# CONFIGURATION_STORAGE_USER_LEDS_BUTTONS.net
KiCad netlist of a schematic drawn in Altium Designer
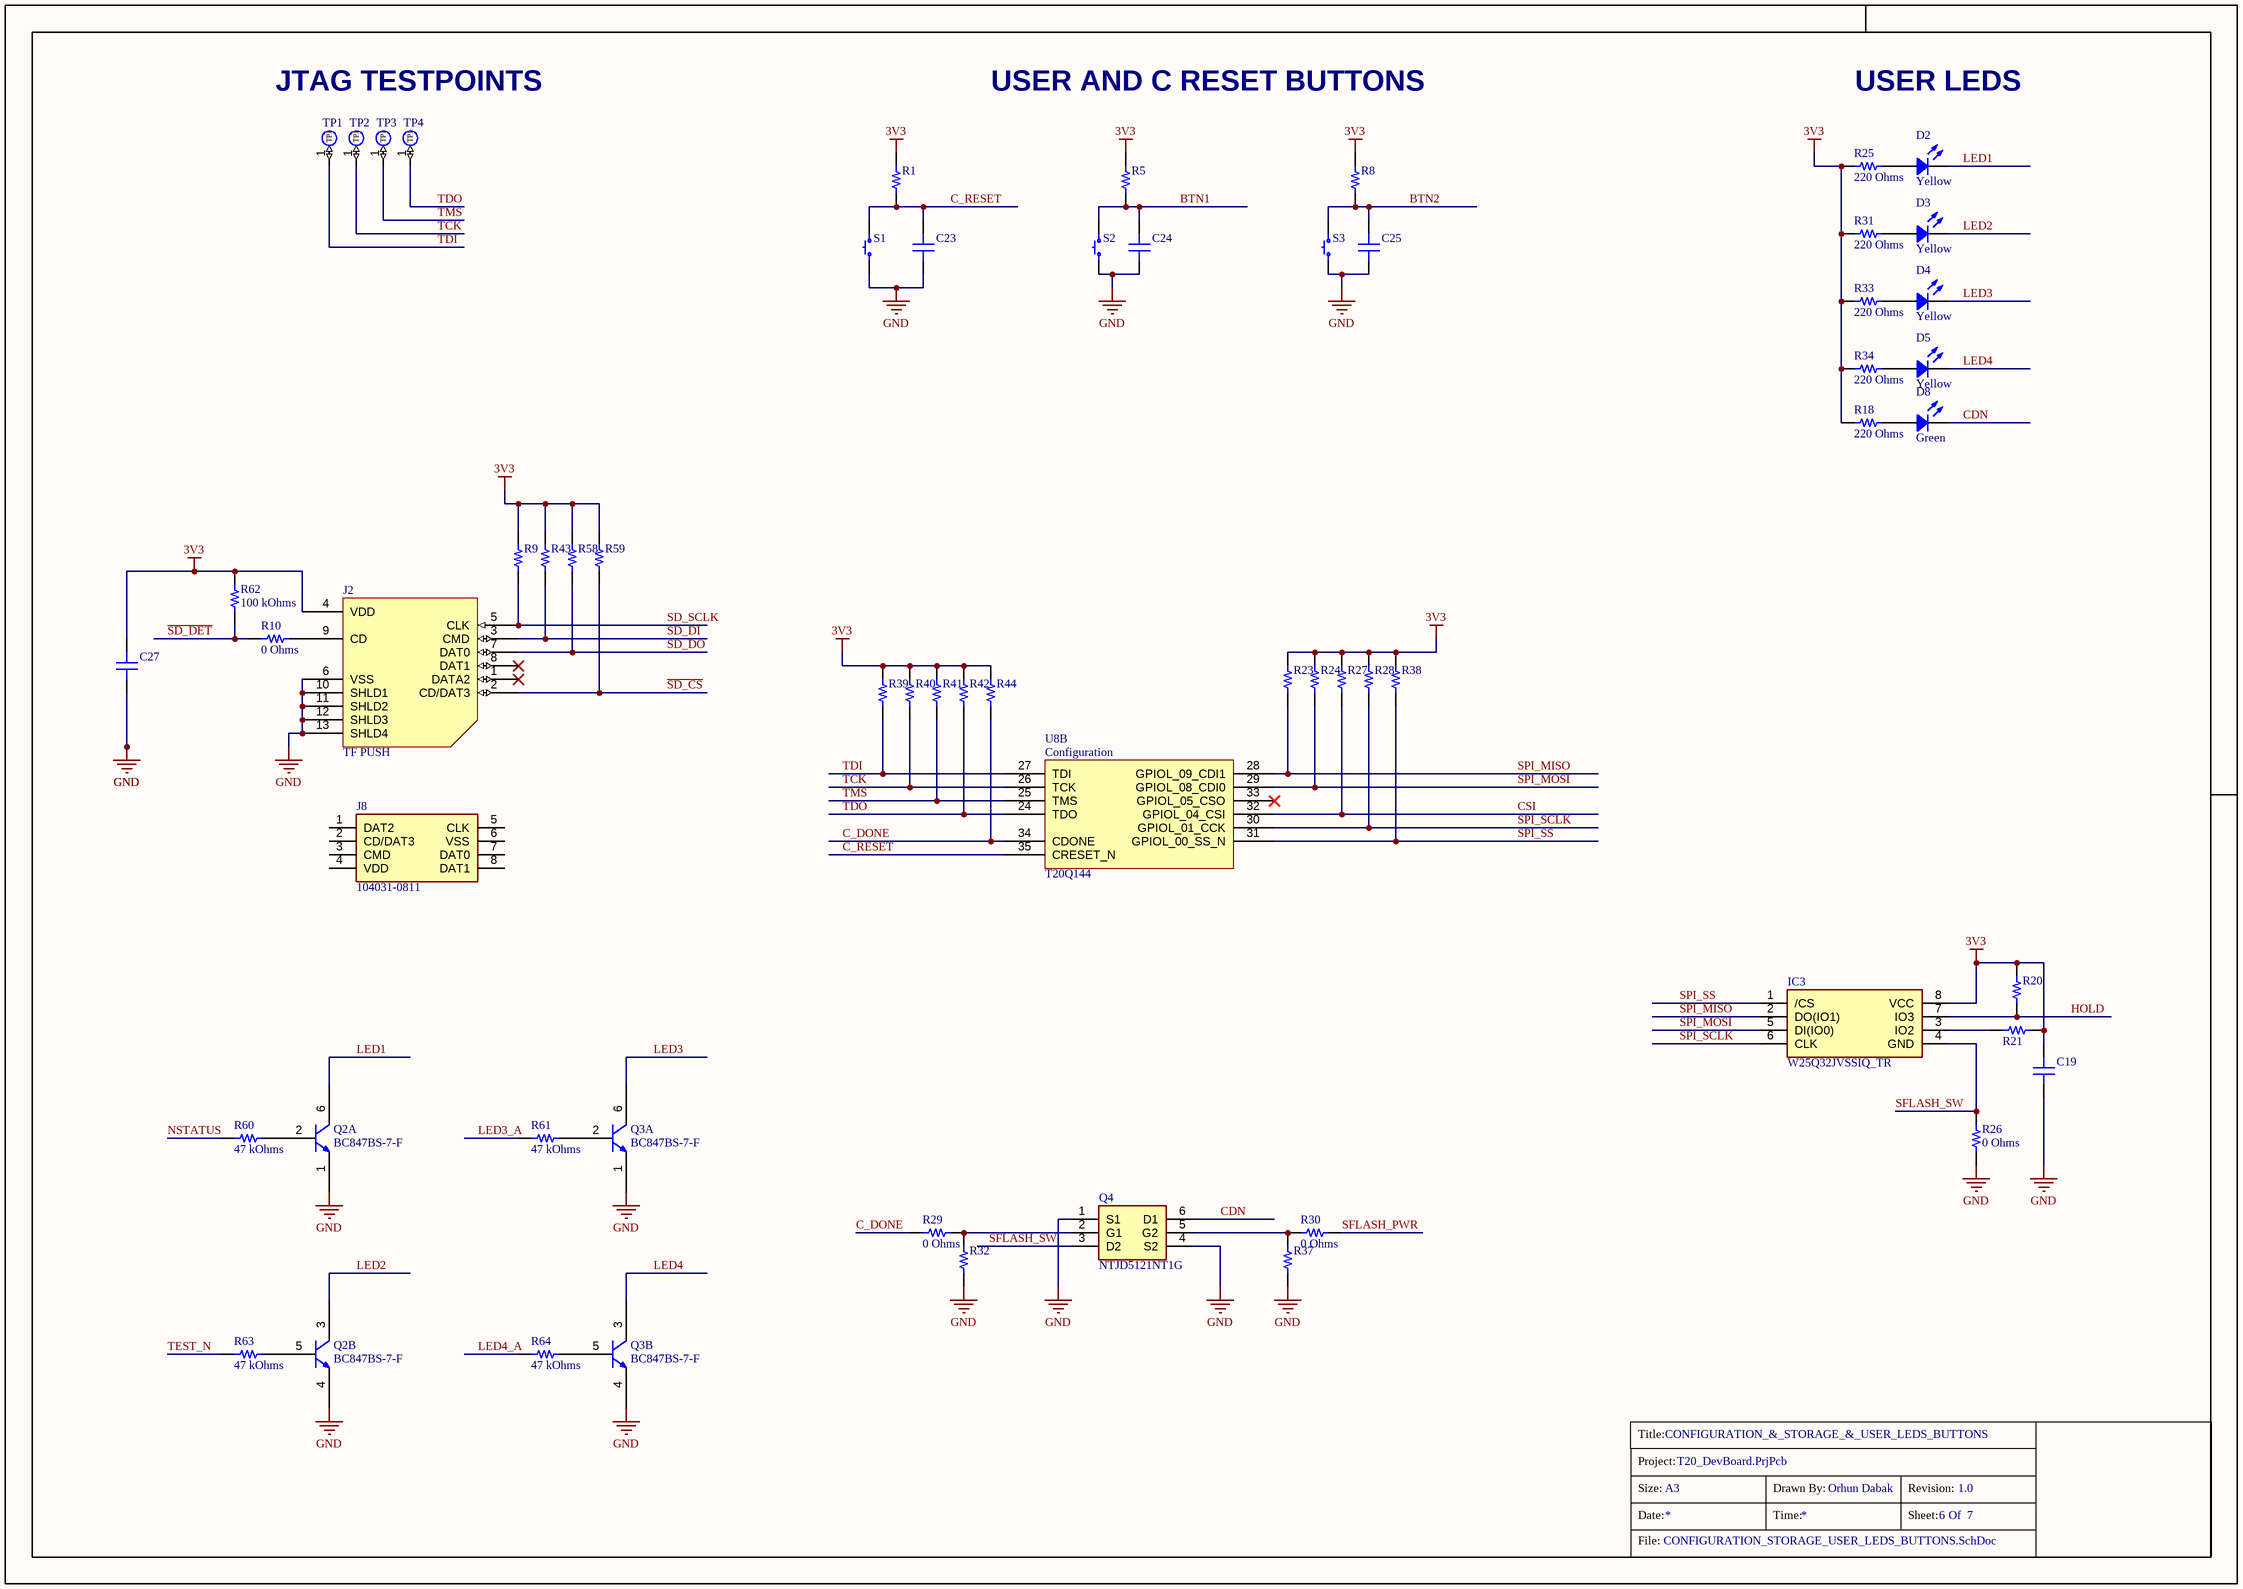
[diagram p0: CONFIGURATION_STORAGE_USER_LEDS_BUTTONS.SchDoc]

(export (version "E")
  (design (tool "Eeschema 10.0.6"))
  (components
    (comp (ref "C19")
      (value "0.1 µF")
      (footprint "CAP 0402_1005")
      (description "CAP CER 0.1UF 10V X7R 0402")
      (fields (field (name "PART NUMBER") "CC0402KRX7R6BB104") (field (name "MANUFACTURER") "Yageo"))
      (libsource (lib "Celestial Altium Library - altium_library") (part "Capacitor"))
    )
    (comp (ref "C23")
      (value "10 µF")
      (footprint "CAP 0402_1005")
      (description "CAP CER 10UF 10V X5R 0402")
      (fields
        (field (name "PART NUMBER") "GRM155R61A106ME11D")
        (field (name "MANUFACTURER") "Murata Electronics")
      )
      (libsource (lib "Celestial Altium Library - altium_library") (part "Capacitor"))
    )
    (comp (ref "C24")
      (value "10 µF")
      (footprint "CAP 0402_1005")
      (description "CAP CER 10UF 10V X5R 0402")
      (fields
        (field (name "PART NUMBER") "GRM155R61A106ME11D")
        (field (name "MANUFACTURER") "Murata Electronics")
      )
      (libsource (lib "Celestial Altium Library - altium_library") (part "Capacitor"))
    )
    (comp (ref "C25")
      (value "10 µF")
      (footprint "CAP 0402_1005")
      (description "CAP CER 10UF 10V X5R 0402")
      (fields
        (field (name "PART NUMBER") "GRM155R61A106ME11D")
        (field (name "MANUFACTURER") "Murata Electronics")
      )
      (libsource (lib "Celestial Altium Library - altium_library") (part "Capacitor"))
    )
    (comp (ref "C27")
      (value "0.1 µF")
      (footprint "CAP 0402_1005")
      (description "CAP CER 0.1UF 10V X7R 0402")
      (fields (field (name "PART NUMBER") "CC0402KRX7R6BB104") (field (name "MANUFACTURER") "Yageo"))
      (libsource (lib "Celestial Altium Library - altium_library") (part "Capacitor"))
    )
    (comp (ref "D2")
      (value "Yellow")
      (footprint "LED 0603_1608 YELLOW")
      (description "LED YELLOW DIFFUSED SMD")
      (fields
        (field (name "PART NUMBER") "SML-LX0603YW-TR")
        (field (name "MANUFACTURER") "Lumex Opto/Components Inc.")
      )
      (libsource (lib "Celestial Altium Library - altium_library") (part "LED"))
    )
    (comp (ref "D3")
      (value "Yellow")
      (footprint "LED 0603_1608 YELLOW")
      (description "LED YELLOW DIFFUSED SMD")
      (fields
        (field (name "PART NUMBER") "SML-LX0603YW-TR")
        (field (name "MANUFACTURER") "Lumex Opto/Components Inc.")
      )
      (libsource (lib "Celestial Altium Library - altium_library") (part "LED"))
    )
    (comp (ref "D4")
      (value "Yellow")
      (footprint "LED 0603_1608 YELLOW")
      (description "LED YELLOW DIFFUSED SMD")
      (fields
        (field (name "PART NUMBER") "SML-LX0603YW-TR")
        (field (name "MANUFACTURER") "Lumex Opto/Components Inc.")
      )
      (libsource (lib "Celestial Altium Library - altium_library") (part "LED"))
    )
    (comp (ref "D5")
      (value "Yellow")
      (footprint "LED 0603_1608 YELLOW")
      (description "LED YELLOW DIFFUSED SMD")
      (fields
        (field (name "PART NUMBER") "SML-LX0603YW-TR")
        (field (name "MANUFACTURER") "Lumex Opto/Components Inc.")
      )
      (libsource (lib "Celestial Altium Library - altium_library") (part "LED"))
    )
    (comp (ref "D8")
      (value "Green")
      (footprint "LED 0603_1608 GREEN")
      (description "LED SM 0603 3V -/1000/-MCD GREEN")
      (fields
        (field (name "PART NUMBER") "LSM0603453V")
        (field (name "MANUFACTURER") "Visual Communications Company - VCC")
      )
      (libsource (lib "Celestial Altium Library - altium_library") (part "LED"))
    )
    (comp (ref "IC3")
      (value "W25Q32JVSSIQ_TR")
      (footprint "SamacSys:SOIC127P790X216-8N")
      (description "Integrated Circuit")
      (fields
        (field (name "MANUFACTURER_PART_NUMBER") "W25Q32JVSSIQ TR")
        (field (name "MOUSER PART NUMBER") "454-W25Q32JVSSIQTR")
      )
      (libsource (lib "SamacSys") (part "W25Q32JVSSIQ_TR"))
    )
    (comp (ref "J2")
      (value "TF PUSH")
      (footprint "TF PUSH")
      (description "-20℃~+90℃ 2mm Deck MicroSD card (TF card) Self bomb SMD SD Card Connectors ROHS")
      (fields (field (name "MANUFACTURER") "SHOU HAN") (field (name "LCSC PART NUMBER") "C393941"))
      (libsource (lib "T8_devkit_PCB") (part "TF PUSH"))
    )
    (comp (ref "J8")
      (value "104031-0811")
      (footprint "SamacSys:1040310811")
      (description "Connector")
      (fields (field (name "MOUSER PART NUMBER") "538-104031-0811"))
      (libsource (lib "*") (part "104031-0811"))
    )
    (comp (ref "Q2")
      (value "BC847BS-7-F")
      (footprint "BC847BS-7-F-Footprint-1")
      (description "2NPN Ic=100mA Vceo=45V hfe=200~450 P=200mW SOT363")
      (libsource (lib "Kocaeli University") (part "BC847BS-7-F-Symbol-1"))
    )
    (comp (ref "Q3")
      (value "BC847BS-7-F")
      (footprint "BC847BS-7-F-Footprint-1")
      (description "2NPN Ic=100mA Vceo=45V hfe=200~450 P=200mW SOT363")
      (libsource (lib "Kocaeli University") (part "BC847BS-7-F-Symbol-1"))
    )
    (comp (ref "Q4")
      (value "NTJD5121NT1G")
      (footprint "SamacSys:SOT65P210X110-6N")
      (description "Transistor")
      (fields (field (name "MOUSER PART NUMBER") "863-NTJD5121NT1G"))
      (libsource (lib "SamacSys") (part "NTJD5121NT1G"))
    )
    (comp (ref "R1")
      (value "10 kOhms")
      (footprint "RES 0402_1005")
      (description "RES 10K OHM 0.1% 1/10W 0402")
      (fields
        (field (name "PART NUMBER") "RP73PF1E10KBTD")
        (field (name "MANUFACTURER") "TE Connectivity Passive Product")
      )
      (libsource (lib "Celestial Altium Library - altium_library") (part "Resistor"))
    )
    (comp (ref "R5")
      (value "10 kOhms")
      (footprint "RES 0402_1005")
      (description "RES 10K OHM 0.1% 1/10W 0402")
      (fields
        (field (name "PART NUMBER") "RP73PF1E10KBTD")
        (field (name "MANUFACTURER") "TE Connectivity Passive Product")
      )
      (libsource (lib "Celestial Altium Library - altium_library") (part "Resistor"))
    )
    (comp (ref "R8")
      (value "10 kOhms")
      (footprint "RES 0402_1005")
      (description "RES 10K OHM 0.1% 1/10W 0402")
      (fields
        (field (name "PART NUMBER") "RP73PF1E10KBTD")
        (field (name "MANUFACTURER") "TE Connectivity Passive Product")
      )
      (libsource (lib "Celestial Altium Library - altium_library") (part "Resistor"))
    )
    (comp (ref "R9")
      (value "10 kOhms")
      (footprint "RES 0402_1005")
      (description "RES 10K OHM 0.1% 1/10W 0402")
      (fields
        (field (name "PART NUMBER") "RP73PF1E10KBTD")
        (field (name "MANUFACTURER") "TE Connectivity Passive Product")
      )
      (libsource (lib "Celestial Altium Library - altium_library") (part "Resistor"))
    )
    (comp (ref "R10")
      (value "0 Ohms")
      (footprint "RES 0402_1005")
      (description "RES 0 OHM JUMPER 1/16W 0402")
      (fields (field (name "PART NUMBER") "RC0402JR-070RL") (field (name "MANUFACTURER") "Yageo"))
      (libsource (lib "Celestial Altium Library - altium_library") (part "Resistor"))
    )
    (comp (ref "R18")
      (value "220 Ohms")
      (footprint "RES 0402_1005")
      (description "RES 220 OHM 1% 1/16W 0402")
      (fields (field (name "PART NUMBER") "RC0402FR-07220RL") (field (name "MANUFACTURER") "Yageo"))
      (libsource (lib "Celestial Altium Library - altium_library") (part "Resistor"))
    )
    (comp (ref "R20")
      (value "10 kOhms")
      (footprint "RES 0402_1005")
      (description "RES 10K OHM 0.1% 1/10W 0402")
      (fields
        (field (name "PART NUMBER") "RP73PF1E10KBTD")
        (field (name "MANUFACTURER") "TE Connectivity Passive Product")
      )
      (libsource (lib "Celestial Altium Library - altium_library") (part "Resistor"))
    )
    (comp (ref "R21")
      (value "10 kOhms")
      (footprint "RES 0402_1005")
      (description "RES 10K OHM 0.1% 1/10W 0402")
      (fields
        (field (name "PART NUMBER") "RP73PF1E10KBTD")
        (field (name "MANUFACTURER") "TE Connectivity Passive Product")
      )
      (libsource (lib "Celestial Altium Library - altium_library") (part "Resistor"))
    )
    (comp (ref "R23")
      (value "10 kOhms")
      (footprint "RES 0402_1005")
      (description "RES 10K OHM 0.1% 1/10W 0402")
      (fields
        (field (name "PART NUMBER") "RP73PF1E10KBTD")
        (field (name "MANUFACTURER") "TE Connectivity Passive Product")
      )
      (libsource (lib "Celestial Altium Library - altium_library") (part "Resistor"))
    )
    (comp (ref "R24")
      (value "10 kOhms")
      (footprint "RES 0402_1005")
      (description "RES 10K OHM 0.1% 1/10W 0402")
      (fields
        (field (name "PART NUMBER") "RP73PF1E10KBTD")
        (field (name "MANUFACTURER") "TE Connectivity Passive Product")
      )
      (libsource (lib "Celestial Altium Library - altium_library") (part "Resistor"))
    )
    (comp (ref "R25")
      (value "220 Ohms")
      (footprint "RES 0402_1005")
      (description "RES 220 OHM 1% 1/16W 0402")
      (fields (field (name "PART NUMBER") "RC0402FR-07220RL") (field (name "MANUFACTURER") "Yageo"))
      (libsource (lib "Celestial Altium Library - altium_library") (part "Resistor"))
    )
    (comp (ref "R26")
      (value "0 Ohms")
      (footprint "RES 0402_1005")
      (description "RES 0 OHM JUMPER 1/16W 0402")
      (fields (field (name "PART NUMBER") "RC0402JR-070RL") (field (name "MANUFACTURER") "Yageo"))
      (libsource (lib "Celestial Altium Library - altium_library") (part "Resistor"))
    )
    (comp (ref "R27")
      (value "10 kOhms")
      (footprint "RES 0402_1005")
      (description "RES 10K OHM 0.1% 1/10W 0402")
      (fields
        (field (name "PART NUMBER") "RP73PF1E10KBTD")
        (field (name "MANUFACTURER") "TE Connectivity Passive Product")
      )
      (libsource (lib "Celestial Altium Library - altium_library") (part "Resistor"))
    )
    (comp (ref "R28")
      (value "10 kOhms")
      (footprint "RES 0402_1005")
      (description "RES 10K OHM 0.1% 1/10W 0402")
      (fields
        (field (name "PART NUMBER") "RP73PF1E10KBTD")
        (field (name "MANUFACTURER") "TE Connectivity Passive Product")
      )
      (libsource (lib "Celestial Altium Library - altium_library") (part "Resistor"))
    )
    (comp (ref "R29")
      (value "0 Ohms")
      (footprint "RES 0402_1005")
      (description "RES 0 OHM JUMPER 1/16W 0402")
      (fields (field (name "PART NUMBER") "RC0402JR-070RL") (field (name "MANUFACTURER") "Yageo"))
      (libsource (lib "Celestial Altium Library - altium_library") (part "Resistor"))
    )
    (comp (ref "R30")
      (value "0 Ohms")
      (footprint "RES 0402_1005")
      (description "RES 0 OHM JUMPER 1/16W 0402")
      (fields (field (name "PART NUMBER") "RC0402JR-070RL") (field (name "MANUFACTURER") "Yageo"))
      (libsource (lib "Celestial Altium Library - altium_library") (part "Resistor"))
    )
    (comp (ref "R31")
      (value "220 Ohms")
      (footprint "RES 0402_1005")
      (description "RES 220 OHM 1% 1/16W 0402")
      (fields (field (name "PART NUMBER") "RC0402FR-07220RL") (field (name "MANUFACTURER") "Yageo"))
      (libsource (lib "Celestial Altium Library - altium_library") (part "Resistor"))
    )
    (comp (ref "R32")
      (value "10 kOhms")
      (footprint "RES 0402_1005")
      (description "RES 10K OHM 0.1% 1/10W 0402")
      (fields
        (field (name "PART NUMBER") "RP73PF1E10KBTD")
        (field (name "MANUFACTURER") "TE Connectivity Passive Product")
      )
      (libsource (lib "Celestial Altium Library - altium_library") (part "Resistor"))
    )
    (comp (ref "R33")
      (value "220 Ohms")
      (footprint "RES 0402_1005")
      (description "RES 220 OHM 1% 1/16W 0402")
      (fields (field (name "PART NUMBER") "RC0402FR-07220RL") (field (name "MANUFACTURER") "Yageo"))
      (libsource (lib "Celestial Altium Library - altium_library") (part "Resistor"))
    )
    (comp (ref "R34")
      (value "220 Ohms")
      (footprint "RES 0402_1005")
      (description "RES 220 OHM 1% 1/16W 0402")
      (fields (field (name "PART NUMBER") "RC0402FR-07220RL") (field (name "MANUFACTURER") "Yageo"))
      (libsource (lib "Celestial Altium Library - altium_library") (part "Resistor"))
    )
    (comp (ref "R37")
      (value "10 kOhms")
      (footprint "RES 0402_1005")
      (description "RES 10K OHM 0.1% 1/10W 0402")
      (fields
        (field (name "PART NUMBER") "RP73PF1E10KBTD")
        (field (name "MANUFACTURER") "TE Connectivity Passive Product")
      )
      (libsource (lib "Celestial Altium Library - altium_library") (part "Resistor"))
    )
    (comp (ref "R38")
      (value "10 kOhms")
      (footprint "RES 0402_1005")
      (description "RES 10K OHM 0.1% 1/10W 0402")
      (fields
        (field (name "PART NUMBER") "RP73PF1E10KBTD")
        (field (name "MANUFACTURER") "TE Connectivity Passive Product")
      )
      (libsource (lib "Celestial Altium Library - altium_library") (part "Resistor"))
    )
    (comp (ref "R39")
      (value "10 kOhms")
      (footprint "RES 0402_1005")
      (description "RES 10K OHM 0.1% 1/10W 0402")
      (fields
        (field (name "PART NUMBER") "RP73PF1E10KBTD")
        (field (name "MANUFACTURER") "TE Connectivity Passive Product")
      )
      (libsource (lib "Celestial Altium Library - altium_library") (part "Resistor"))
    )
    (comp (ref "R40")
      (value "10 kOhms")
      (footprint "RES 0402_1005")
      (description "RES 10K OHM 0.1% 1/10W 0402")
      (fields
        (field (name "PART NUMBER") "RP73PF1E10KBTD")
        (field (name "MANUFACTURER") "TE Connectivity Passive Product")
      )
      (libsource (lib "Celestial Altium Library - altium_library") (part "Resistor"))
    )
    (comp (ref "R41")
      (value "10 kOhms")
      (footprint "RES 0402_1005")
      (description "RES 10K OHM 0.1% 1/10W 0402")
      (fields
        (field (name "PART NUMBER") "RP73PF1E10KBTD")
        (field (name "MANUFACTURER") "TE Connectivity Passive Product")
      )
      (libsource (lib "Celestial Altium Library - altium_library") (part "Resistor"))
    )
    (comp (ref "R42")
      (value "10 kOhms")
      (footprint "RES 0402_1005")
      (description "RES 10K OHM 0.1% 1/10W 0402")
      (fields
        (field (name "PART NUMBER") "RP73PF1E10KBTD")
        (field (name "MANUFACTURER") "TE Connectivity Passive Product")
      )
      (libsource (lib "Celestial Altium Library - altium_library") (part "Resistor"))
    )
    (comp (ref "R43")
      (value "10 kOhms")
      (footprint "RES 0402_1005")
      (description "RES 10K OHM 0.1% 1/10W 0402")
      (fields
        (field (name "PART NUMBER") "RP73PF1E10KBTD")
        (field (name "MANUFACTURER") "TE Connectivity Passive Product")
      )
      (libsource (lib "Celestial Altium Library - altium_library") (part "Resistor"))
    )
    (comp (ref "R44")
      (value "10 kOhms")
      (footprint "RES 0402_1005")
      (description "RES 10K OHM 0.1% 1/10W 0402")
      (fields
        (field (name "PART NUMBER") "RP73PF1E10KBTD")
        (field (name "MANUFACTURER") "TE Connectivity Passive Product")
      )
      (libsource (lib "Celestial Altium Library - altium_library") (part "Resistor"))
    )
    (comp (ref "R58")
      (value "10 kOhms")
      (footprint "RES 0402_1005")
      (description "RES 10K OHM 0.1% 1/10W 0402")
      (fields
        (field (name "PART NUMBER") "RP73PF1E10KBTD")
        (field (name "MANUFACTURER") "TE Connectivity Passive Product")
      )
      (libsource (lib "Celestial Altium Library - altium_library") (part "Resistor"))
    )
    (comp (ref "R59")
      (value "10 kOhms")
      (footprint "RES 0402_1005")
      (description "RES 10K OHM 0.1% 1/10W 0402")
      (fields
        (field (name "PART NUMBER") "RP73PF1E10KBTD")
        (field (name "MANUFACTURER") "TE Connectivity Passive Product")
      )
      (libsource (lib "Celestial Altium Library - altium_library") (part "Resistor"))
    )
    (comp (ref "R60")
      (value "47 kOhms")
      (footprint "RES 0402_1005")
      (description "RES 47K OHM 1% 1/16W 0402")
      (fields
        (field (name "PART NUMBER") "RMCF0402FT47K0")
        (field (name "MANUFACTURER") "Stackpole Electronics Inc")
      )
      (libsource (lib "Celestial Altium Library - altium_library") (part "Resistor"))
    )
    (comp (ref "R61")
      (value "47 kOhms")
      (footprint "RES 0402_1005")
      (description "RES 47K OHM 1% 1/16W 0402")
      (fields
        (field (name "PART NUMBER") "RMCF0402FT47K0")
        (field (name "MANUFACTURER") "Stackpole Electronics Inc")
      )
      (libsource (lib "Celestial Altium Library - altium_library") (part "Resistor"))
    )
    (comp (ref "R62")
      (value "100 kOhms")
      (footprint "RES 0402_1005")
      (description "RES SMD 100K OHM 1% 1/16W 0402")
      (fields (field (name "PART NUMBER") "RT0402FRE07100KL") (field (name "MANUFACTURER") "Yageo"))
      (libsource (lib "Celestial Altium Library - altium_library") (part "Resistor"))
    )
    (comp (ref "R63")
      (value "47 kOhms")
      (footprint "RES 0402_1005")
      (description "RES 47K OHM 1% 1/16W 0402")
      (fields
        (field (name "PART NUMBER") "RMCF0402FT47K0")
        (field (name "MANUFACTURER") "Stackpole Electronics Inc")
      )
      (libsource (lib "Celestial Altium Library - altium_library") (part "Resistor"))
    )
    (comp (ref "R64")
      (value "47 kOhms")
      (footprint "RES 0402_1005")
      (description "RES 47K OHM 1% 1/16W 0402")
      (fields
        (field (name "PART NUMBER") "RMCF0402FT47K0")
        (field (name "MANUFACTURER") "Stackpole Electronics Inc")
      )
      (libsource (lib "Celestial Altium Library - altium_library") (part "Resistor"))
    )
    (comp (ref "S1")
      (value "TS342A2P-WZ")
      (footprint "TS342A2P-WZ")
      (fields (field (name "MANUFACTURER") "SHOU HAN") (field (name "JLCPCB PART NUMBER") "C557591"))
      (libsource (lib "T8_devkit_PCB") (part "TS342A2P-WZ"))
    )
    (comp (ref "S2")
      (value "TS342A2P-WZ")
      (footprint "TS342A2P-WZ")
      (fields (field (name "MANUFACTURER") "SHOU HAN") (field (name "JLCPCB PART NUMBER") "C557591"))
      (libsource (lib "T8_devkit_PCB") (part "TS342A2P-WZ"))
    )
    (comp (ref "S3")
      (value "TS342A2P-WZ")
      (footprint "TS342A2P-WZ")
      (fields (field (name "MANUFACTURER") "SHOU HAN") (field (name "JLCPCB PART NUMBER") "C557591"))
      (libsource (lib "T8_devkit_PCB") (part "TS342A2P-WZ"))
    )
    (comp (ref "TP1")
      (value "TP_1")
      (footprint "TEST POINT")
      (description "1.5x1.5mm Test Point(I/O)")
      (libsource (lib "FPGA_Based_SOM") (part "TEST POINT_1(I/O)"))
    )
    (comp (ref "TP2")
      (value "TP_1")
      (footprint "TEST POINT")
      (description "1.5x1.5mm Test Point(I/O)")
      (libsource (lib "FPGA_Based_SOM") (part "TEST POINT_1(I/O)"))
    )
    (comp (ref "TP3")
      (value "TP_1")
      (footprint "TEST POINT")
      (description "1.5x1.5mm Test Point(I/O)")
      (libsource (lib "FPGA_Based_SOM") (part "TEST POINT_1(I/O)"))
    )
    (comp (ref "TP4")
      (value "TP_1")
      (footprint "TEST POINT")
      (description "1.5x1.5mm Test Point(I/O)")
      (libsource (lib "FPGA_Based_SOM") (part "TEST POINT_1(I/O)"))
    )
    (comp (ref "U8")
      (value "T20Q144")
      (footprint "T8_devkit_PCB:CQFP50P2200X2200X160-144N")
      (description "Trion® Field Programmable Gate Array (FPGA) IC 97 1044 19728 144-LQFP")
      (libsource (lib "T8_devkit_PCB") (part "T20Q144"))
    )
  )
  (nets
    (net (code "1") (name "/BTN1") (class "Default")
      (node (ref "C24") (pin "2") (pinfunction "2_2") (pintype "passive"))
      (node (ref "R5") (pin "1") (pinfunction "1_1") (pintype "passive"))
      (node (ref "S2") (pin "2") (pinfunction "2_2") (pintype "passive"))
    )
    (net (code "2") (name "/BTN2") (class "Default")
      (node (ref "C25") (pin "2") (pinfunction "2_2") (pintype "passive"))
      (node (ref "R8") (pin "1") (pinfunction "1_1") (pintype "passive"))
      (node (ref "S3") (pin "2") (pinfunction "2_2") (pintype "passive"))
    )
    (net (code "3") (name "/CDN") (class "Default")
      (node (ref "D8") (pin "2") (pinfunction "2_2") (pintype "passive"))
      (node (ref "Q4") (pin "6") (pinfunction "D1_6") (pintype "passive"))
    )
    (net (code "4") (name "/CSI") (class "Default")
      (node (ref "R27") (pin "1") (pinfunction "1_1") (pintype "passive"))
      (node (ref "U8") (pin "32") (pinfunction "GPIOL_04_CSI_32") (pintype "passive"))
    )
    (net (code "5") (name "/C_DONE") (class "Default")
      (node (ref "R29") (pin "1") (pinfunction "1_1") (pintype "passive"))
      (node (ref "R44") (pin "1") (pinfunction "1_1") (pintype "passive"))
      (node (ref "U8") (pin "34") (pinfunction "CDONE_34") (pintype "passive"))
    )
    (net (code "6") (name "/C_RESET") (class "Default")
      (node (ref "C23") (pin "2") (pinfunction "2_2") (pintype "passive"))
      (node (ref "R1") (pin "1") (pinfunction "1_1") (pintype "passive"))
      (node (ref "S1") (pin "2") (pinfunction "2_2") (pintype "passive"))
      (node (ref "U8") (pin "35") (pinfunction "CRESET_N_35") (pintype "passive"))
    )
    (net (code "7") (name "/HOLD") (class "Default")
      (node (ref "IC3") (pin "7") (pinfunction "IO3_7") (pintype "passive"))
      (node (ref "R20") (pin "1") (pinfunction "1_1") (pintype "passive"))
    )
    (net (code "8") (name "/LED1") (class "Default")
      (node (ref "D2") (pin "2") (pinfunction "2_2") (pintype "passive"))
      (node (ref "Q2") (pin "6") (pinfunction "Collector_6") (pintype "passive"))
    )
    (net (code "9") (name "/LED2") (class "Default")
      (node (ref "D3") (pin "2") (pinfunction "2_2") (pintype "passive"))
      (node (ref "Q2") (pin "3") (pinfunction "Collector_3") (pintype "passive"))
    )
    (net (code "10") (name "/LED3") (class "Default")
      (node (ref "D4") (pin "2") (pinfunction "2_2") (pintype "passive"))
      (node (ref "Q3") (pin "6") (pinfunction "Collector_6") (pintype "passive"))
    )
    (net (code "11") (name "/LED3_A") (class "Default")
      (node (ref "R61") (pin "1") (pinfunction "1_1") (pintype "passive"))
    )
    (net (code "12") (name "/LED4") (class "Default")
      (node (ref "D5") (pin "2") (pinfunction "2_2") (pintype "passive"))
      (node (ref "Q3") (pin "3") (pinfunction "Collector_3") (pintype "passive"))
    )
    (net (code "13") (name "/LED4_A") (class "Default")
      (node (ref "R64") (pin "1") (pinfunction "1_1") (pintype "passive"))
    )
    (net (code "14") (name "/NSTATUS") (class "Default")
      (node (ref "R60") (pin "1") (pinfunction "1_1") (pintype "passive"))
    )
    (net (code "15") (name "/SD_DI") (class "Default")
      (node (ref "J2") (pin "3") (pinfunction "CMD_3") (pintype "bidirectional"))
      (node (ref "R43") (pin "1") (pinfunction "1_1") (pintype "passive"))
    )
    (net (code "16") (name "/SD_DO") (class "Default")
      (node (ref "J2") (pin "7") (pinfunction "DAT0_7") (pintype "bidirectional"))
      (node (ref "R58") (pin "1") (pinfunction "1_1") (pintype "passive"))
    )
    (net (code "17") (name "/SD_SCLK") (class "Default")
      (node (ref "J2") (pin "5") (pinfunction "CLK_5") (pintype "input"))
      (node (ref "R9") (pin "1") (pinfunction "1_1") (pintype "passive"))
    )
    (net (code "18") (name "/SFLASH_PWR") (class "Default")
      (node (ref "R30") (pin "2") (pinfunction "2_2") (pintype "passive"))
    )
    (net (code "19") (name "/SFLASH_SW") (class "Default")
      (node (ref "IC3") (pin "4") (pinfunction "GND_4") (pintype "passive"))
      (node (ref "Q4") (pin "3") (pinfunction "D2_3") (pintype "passive"))
      (node (ref "R26") (pin "2") (pinfunction "2_2") (pintype "passive"))
    )
    (net (code "20") (name "/SPI_MISO") (class "Default")
      (node (ref "IC3") (pin "2") (pinfunction "DO(IO1)_2") (pintype "passive"))
      (node (ref "R23") (pin "1") (pinfunction "1_1") (pintype "passive"))
      (node (ref "U8") (pin "28") (pinfunction "GPIOL_09_CDI1_28") (pintype "passive"))
    )
    (net (code "21") (name "/SPI_MOSI") (class "Default")
      (node (ref "IC3") (pin "5") (pinfunction "DI(IO0)_5") (pintype "passive"))
      (node (ref "R24") (pin "1") (pinfunction "1_1") (pintype "passive"))
      (node (ref "U8") (pin "29") (pinfunction "GPIOL_08_CDI0_29") (pintype "passive"))
    )
    (net (code "22") (name "/SPI_SCLK") (class "Default")
      (node (ref "IC3") (pin "6") (pinfunction "CLK_6") (pintype "passive"))
      (node (ref "R28") (pin "1") (pinfunction "1_1") (pintype "passive"))
      (node (ref "U8") (pin "30") (pinfunction "GPIOL_01_CCK_30") (pintype "passive"))
    )
    (net (code "23") (name "/SPI_SS") (class "Default")
      (node (ref "IC3") (pin "1") (pinfunction "/CS_1") (pintype "passive"))
      (node (ref "R38") (pin "1") (pinfunction "1_1") (pintype "passive"))
      (node (ref "U8") (pin "31") (pinfunction "GPIOL_00_SS_N_31") (pintype "passive"))
    )
    (net (code "24") (name "/TCK") (class "Default")
      (node (ref "R40") (pin "1") (pinfunction "1_1") (pintype "passive"))
      (node (ref "TP2") (pin "1") (pinfunction "TP1_1") (pintype "bidirectional"))
      (node (ref "U8") (pin "26") (pinfunction "TCK_26") (pintype "passive"))
    )
    (net (code "25") (name "/TDI") (class "Default")
      (node (ref "R39") (pin "1") (pinfunction "1_1") (pintype "passive"))
      (node (ref "TP1") (pin "1") (pinfunction "TP1_1") (pintype "bidirectional"))
      (node (ref "U8") (pin "27") (pinfunction "TDI_27") (pintype "passive"))
    )
    (net (code "26") (name "/TDO") (class "Default")
      (node (ref "R42") (pin "1") (pinfunction "1_1") (pintype "passive"))
      (node (ref "TP4") (pin "1") (pinfunction "TP1_1") (pintype "bidirectional"))
      (node (ref "U8") (pin "24") (pinfunction "TDO_24") (pintype "passive"))
    )
    (net (code "27") (name "/TEST_N") (class "Default")
      (node (ref "R63") (pin "1") (pinfunction "1_1") (pintype "passive"))
    )
    (net (code "28") (name "/TMS") (class "Default")
      (node (ref "R41") (pin "1") (pinfunction "1_1") (pintype "passive"))
      (node (ref "TP3") (pin "1") (pinfunction "TP1_1") (pintype "bidirectional"))
      (node (ref "U8") (pin "25") (pinfunction "TMS_25") (pintype "passive"))
    )
    (net (code "29") (name "/~{SD_CS}") (class "Default")
      (node (ref "J2") (pin "2") (pinfunction "CD/DAT3_2") (pintype "bidirectional"))
      (node (ref "R59") (pin "1") (pinfunction "1_1") (pintype "passive"))
    )
    (net (code "30") (name "/~{SD_DET}") (class "Default")
      (node (ref "R10") (pin "1") (pinfunction "1_1") (pintype "passive"))
      (node (ref "R62") (pin "1") (pinfunction "1_1") (pintype "passive"))
    )
    (net (code "31") (name "3V3") (class "Default")
      (node (ref "C19") (pin "2") (pinfunction "2_2") (pintype "passive"))
      (node (ref "C27") (pin "2") (pinfunction "2_2") (pintype "passive"))
      (node (ref "IC3") (pin "8") (pinfunction "VCC_8") (pintype "passive"))
      (node (ref "J2") (pin "4") (pinfunction "VDD_4") (pintype "power_in"))
      (node (ref "R1") (pin "2") (pinfunction "2_2") (pintype "passive"))
      (node (ref "R18") (pin "1") (pinfunction "1_1") (pintype "passive"))
      (node (ref "R20") (pin "2") (pinfunction "2_2") (pintype "passive"))
      (node (ref "R21") (pin "1") (pinfunction "1_1") (pintype "passive"))
      (node (ref "R23") (pin "2") (pinfunction "2_2") (pintype "passive"))
      (node (ref "R24") (pin "2") (pinfunction "2_2") (pintype "passive"))
      (node (ref "R25") (pin "1") (pinfunction "1_1") (pintype "passive"))
      (node (ref "R27") (pin "2") (pinfunction "2_2") (pintype "passive"))
      (node (ref "R28") (pin "2") (pinfunction "2_2") (pintype "passive"))
      (node (ref "R31") (pin "1") (pinfunction "1_1") (pintype "passive"))
      (node (ref "R33") (pin "1") (pinfunction "1_1") (pintype "passive"))
      (node (ref "R34") (pin "1") (pinfunction "1_1") (pintype "passive"))
      (node (ref "R38") (pin "2") (pinfunction "2_2") (pintype "passive"))
      (node (ref "R39") (pin "2") (pinfunction "2_2") (pintype "passive"))
      (node (ref "R40") (pin "2") (pinfunction "2_2") (pintype "passive"))
      (node (ref "R41") (pin "2") (pinfunction "2_2") (pintype "passive"))
      (node (ref "R42") (pin "2") (pinfunction "2_2") (pintype "passive"))
      (node (ref "R43") (pin "2") (pinfunction "2_2") (pintype "passive"))
      (node (ref "R44") (pin "2") (pinfunction "2_2") (pintype "passive"))
      (node (ref "R5") (pin "2") (pinfunction "2_2") (pintype "passive"))
      (node (ref "R58") (pin "2") (pinfunction "2_2") (pintype "passive"))
      (node (ref "R59") (pin "2") (pinfunction "2_2") (pintype "passive"))
      (node (ref "R62") (pin "2") (pinfunction "2_2") (pintype "passive"))
      (node (ref "R8") (pin "2") (pinfunction "2_2") (pintype "passive"))
      (node (ref "R9") (pin "2") (pinfunction "2_2") (pintype "passive"))
    )
    (net (code "32") (name "GND") (class "Default")
      (node (ref "C19") (pin "1") (pinfunction "1_1") (pintype "passive"))
      (node (ref "C23") (pin "1") (pinfunction "1_1") (pintype "passive"))
      (node (ref "C24") (pin "1") (pinfunction "1_1") (pintype "passive"))
      (node (ref "C25") (pin "1") (pinfunction "1_1") (pintype "passive"))
      (node (ref "C27") (pin "1") (pinfunction "1_1") (pintype "passive"))
      (node (ref "J2") (pin "10") (pinfunction "SHLD1_10") (pintype "passive"))
      (node (ref "J2") (pin "11") (pinfunction "SHLD2_11") (pintype "passive"))
      (node (ref "J2") (pin "12") (pinfunction "SHLD3_12") (pintype "passive"))
      (node (ref "J2") (pin "13") (pinfunction "SHLD4_13") (pintype "passive"))
      (node (ref "J2") (pin "6") (pinfunction "VSS_6") (pintype "power_in"))
      (node (ref "Q2") (pin "1") (pinfunction "Emitter_1") (pintype "passive"))
      (node (ref "Q2") (pin "4") (pinfunction "Emitter_4") (pintype "passive"))
      (node (ref "Q3") (pin "1") (pinfunction "Emitter_1") (pintype "passive"))
      (node (ref "Q3") (pin "4") (pinfunction "Emitter_4") (pintype "passive"))
      (node (ref "Q4") (pin "1") (pinfunction "S1_1") (pintype "passive"))
      (node (ref "Q4") (pin "4") (pinfunction "S2_4") (pintype "passive"))
      (node (ref "R26") (pin "1") (pinfunction "1_1") (pintype "passive"))
      (node (ref "R32") (pin "1") (pinfunction "1_1") (pintype "passive"))
      (node (ref "R37") (pin "1") (pinfunction "1_1") (pintype "passive"))
      (node (ref "S1") (pin "1") (pinfunction "1_1") (pintype "passive"))
      (node (ref "S2") (pin "1") (pinfunction "1_1") (pintype "passive"))
      (node (ref "S3") (pin "1") (pinfunction "1_1") (pintype "passive"))
    )
    (net (code "33") (name "Net-(D2-Pad1)") (class "Default")
      (node (ref "D2") (pin "1") (pinfunction "1_1") (pintype "passive"))
      (node (ref "R25") (pin "2") (pinfunction "2_2") (pintype "passive"))
    )
    (net (code "34") (name "Net-(D3-Pad1)") (class "Default")
      (node (ref "D3") (pin "1") (pinfunction "1_1") (pintype "passive"))
      (node (ref "R31") (pin "2") (pinfunction "2_2") (pintype "passive"))
    )
    (net (code "35") (name "Net-(D4-Pad1)") (class "Default")
      (node (ref "D4") (pin "1") (pinfunction "1_1") (pintype "passive"))
      (node (ref "R33") (pin "2") (pinfunction "2_2") (pintype "passive"))
    )
    (net (code "36") (name "Net-(D5-Pad1)") (class "Default")
      (node (ref "D5") (pin "1") (pinfunction "1_1") (pintype "passive"))
      (node (ref "R34") (pin "2") (pinfunction "2_2") (pintype "passive"))
    )
    (net (code "37") (name "Net-(D8-Pad1)") (class "Default")
      (node (ref "D8") (pin "1") (pinfunction "1_1") (pintype "passive"))
      (node (ref "R18") (pin "2") (pinfunction "2_2") (pintype "passive"))
    )
    (net (code "38") (name "Net-(IC3-IO2)") (class "Default")
      (node (ref "IC3") (pin "3") (pinfunction "IO2_3") (pintype "passive"))
      (node (ref "R21") (pin "2") (pinfunction "2_2") (pintype "passive"))
    )
    (net (code "39") (name "Net-(J2-CD)") (class "Default")
      (node (ref "J2") (pin "9") (pinfunction "CD_9") (pintype "passive"))
      (node (ref "R10") (pin "2") (pinfunction "2_2") (pintype "passive"))
    )
    (net (code "40") (name "Net-(Q2A-Base)") (class "Default")
      (node (ref "Q2") (pin "2") (pinfunction "Base_2") (pintype "passive"))
      (node (ref "R60") (pin "2") (pinfunction "2_2") (pintype "passive"))
    )
    (net (code "41") (name "Net-(Q2B-Base)") (class "Default")
      (node (ref "Q2") (pin "5") (pinfunction "Base_5") (pintype "passive"))
      (node (ref "R63") (pin "2") (pinfunction "2_2") (pintype "passive"))
    )
    (net (code "42") (name "Net-(Q3A-Base)") (class "Default")
      (node (ref "Q3") (pin "2") (pinfunction "Base_2") (pintype "passive"))
      (node (ref "R61") (pin "2") (pinfunction "2_2") (pintype "passive"))
    )
    (net (code "43") (name "Net-(Q3B-Base)") (class "Default")
      (node (ref "Q3") (pin "5") (pinfunction "Base_5") (pintype "passive"))
      (node (ref "R64") (pin "2") (pinfunction "2_2") (pintype "passive"))
    )
    (net (code "44") (name "Net-(Q4-G1)") (class "Default")
      (node (ref "Q4") (pin "2") (pinfunction "G1_2") (pintype "passive"))
      (node (ref "R29") (pin "2") (pinfunction "2_2") (pintype "passive"))
      (node (ref "R32") (pin "2") (pinfunction "2_2") (pintype "passive"))
    )
    (net (code "45") (name "Net-(Q4-G2)") (class "Default")
      (node (ref "Q4") (pin "5") (pinfunction "G2_5") (pintype "passive"))
      (node (ref "R30") (pin "1") (pinfunction "1_1") (pintype "passive"))
      (node (ref "R37") (pin "2") (pinfunction "2_2") (pintype "passive"))
    )
    (net (code "46") (name "unconnected-(J2-DAT1-Pad8)") (class "Default")
      (node (ref "J2") (pin "8") (pinfunction "DAT1_8") (pintype "bidirectional+no_connect"))
    )
    (net (code "47") (name "unconnected-(J2-DATA2-Pad1)") (class "Default")
      (node (ref "J2") (pin "1") (pinfunction "DATA2_1") (pintype "bidirectional+no_connect"))
    )
    (net (code "48") (name "unconnected-(J8-CD{slash}DAT3-Pad2)") (class "Default")
      (node (ref "J8") (pin "2") (pinfunction "CD/DAT3_2") (pintype "passive"))
    )
    (net (code "49") (name "unconnected-(J8-CLK-Pad5)") (class "Default")
      (node (ref "J8") (pin "5") (pinfunction "CLK_5") (pintype "passive"))
    )
    (net (code "50") (name "unconnected-(J8-CMD-Pad3)") (class "Default")
      (node (ref "J8") (pin "3") (pinfunction "CMD_3") (pintype "passive"))
    )
    (net (code "51") (name "unconnected-(J8-DAT0-Pad7)") (class "Default")
      (node (ref "J8") (pin "7") (pinfunction "DAT0_7") (pintype "passive"))
    )
    (net (code "52") (name "unconnected-(J8-DAT1-Pad8)") (class "Default")
      (node (ref "J8") (pin "8") (pinfunction "DAT1_8") (pintype "passive"))
    )
    (net (code "53") (name "unconnected-(J8-DAT2-Pad1)") (class "Default")
      (node (ref "J8") (pin "1") (pinfunction "DAT2_1") (pintype "passive"))
    )
    (net (code "54") (name "unconnected-(J8-VDD-Pad4)") (class "Default")
      (node (ref "J8") (pin "4") (pinfunction "VDD_4") (pintype "passive"))
    )
    (net (code "55") (name "unconnected-(J8-VSS-Pad6)") (class "Default")
      (node (ref "J8") (pin "6") (pinfunction "VSS_6") (pintype "passive"))
    )
    (net (code "56") (name "unconnected-(U8B-GPIOL_05_CSO-Pad33)") (class "Default")
      (node (ref "U8") (pin "33") (pinfunction "GPIOL_05_CSO_33") (pintype "passive+no_connect"))
    )
  )
)
